# old_contorol_board.net
KiCad netlist of a schematic drawn in EAGLE
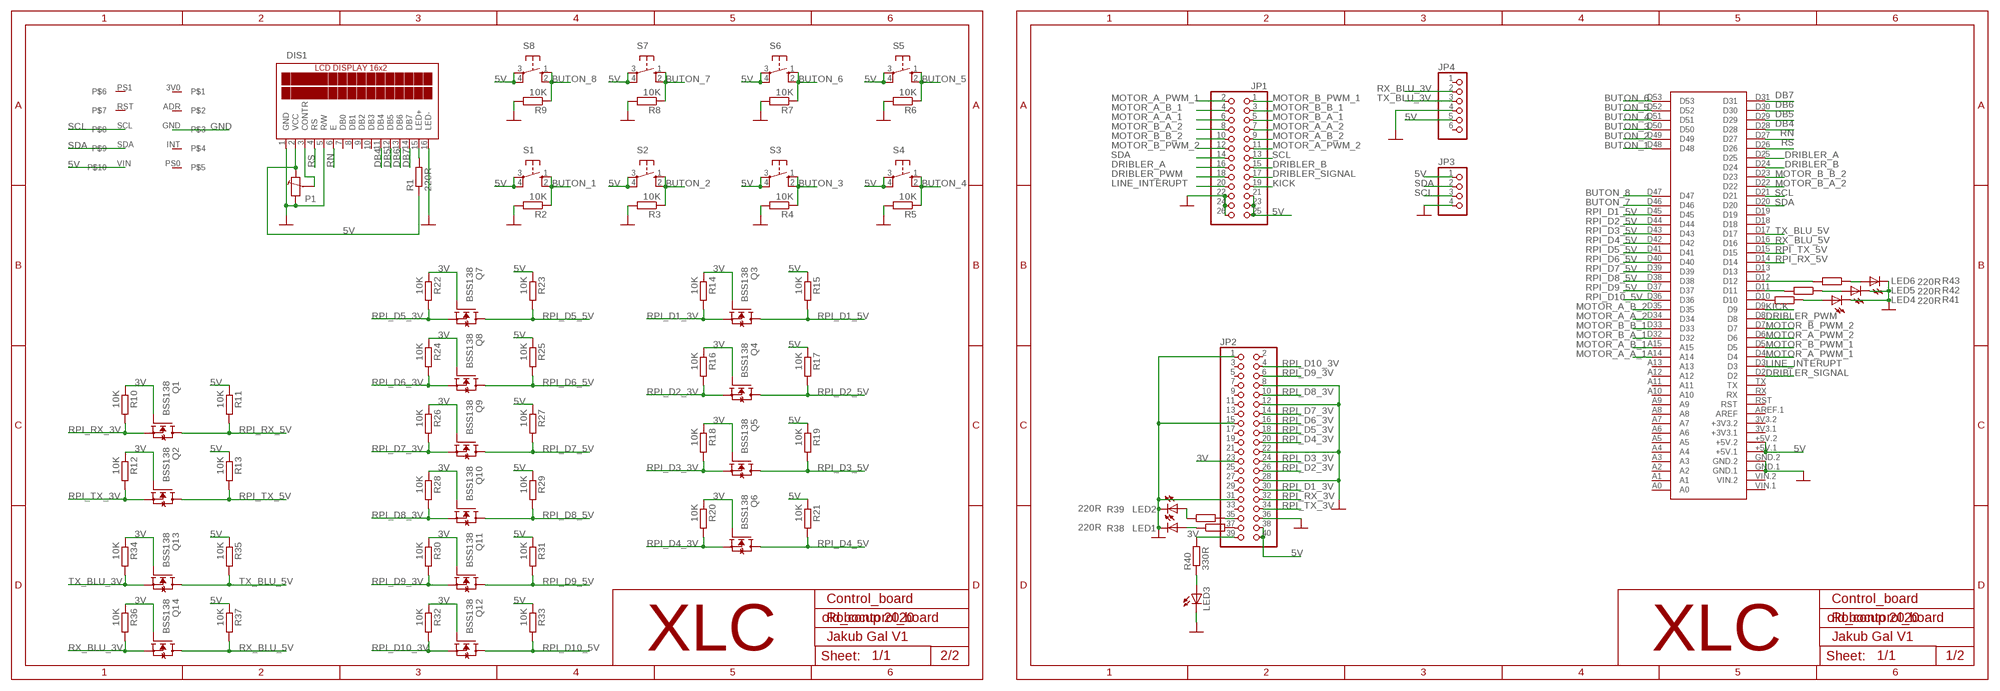
[diagram p0: schematic, sheet 1]

(export (version "E")
  (design (tool "Eeschema 10.0.6"))
  (components
    (comp (ref "DIS1")
      (value "LCD_DISPLEJ_16X2Z")
      (footprint "eagle-import:LCD_DISPLEJ_16X2")
      (libsource (lib "eagle-import") (part "LCD_DISPLEJ_16X2Z"))
    )
    (comp (ref "JP1")
      (value "PINHD-2X13_2.54")
      (footprint "eagle-import:2X13")
      (libsource (lib "eagle-import") (part "PINHD-2X13_2.54"))
    )
    (comp (ref "JP2")
      (value "PINHD-2X20_2.54")
      (footprint "eagle-import:2X20")
      (libsource (lib "eagle-import") (part "PINHD-2X20_2.54"))
    )
    (comp (ref "JP3")
      (value "PINHD-1X4_2.54")
      (footprint "eagle-import:1X04")
      (libsource (lib "eagle-import") (part "PINHD-1X4_2.54"))
    )
    (comp (ref "JP4")
      (value "PINHD-1X6_2.54")
      (footprint "eagle-import:1X06")
      (libsource (lib "eagle-import") (part "PINHD-1X6_2.54"))
    )
    (comp (ref "LED1")
      (value "LEDCHIPLED_0603")
      (footprint "eagle-import:CHIPLED_0603")
      (libsource (lib "eagle-import") (part "LEDCHIPLED_0603"))
    )
    (comp (ref "LED2")
      (value "LEDCHIPLED_0603")
      (footprint "eagle-import:CHIPLED_0603")
      (libsource (lib "eagle-import") (part "LEDCHIPLED_0603"))
    )
    (comp (ref "LED3")
      (value "LEDCHIPLED_0603")
      (footprint "eagle-import:CHIPLED_0603")
      (libsource (lib "eagle-import") (part "LEDCHIPLED_0603"))
    )
    (comp (ref "LED4")
      (value "LEDCHIPLED_0603")
      (footprint "eagle-import:CHIPLED_0603")
      (libsource (lib "eagle-import") (part "LEDCHIPLED_0603"))
    )
    (comp (ref "LED5")
      (value "LEDCHIPLED_0603")
      (footprint "eagle-import:CHIPLED_0603")
      (libsource (lib "eagle-import") (part "LEDCHIPLED_0603"))
    )
    (comp (ref "LED6")
      (value "LEDCHIPLED_0603")
      (footprint "eagle-import:CHIPLED_0603")
      (libsource (lib "eagle-import") (part "LEDCHIPLED_0603"))
    )
    (comp (ref "P1")
      (value "TRIMER-CA6V")
      (footprint "eagle-import:TP-CA6V")
      (libsource (lib "eagle-import") (part "TRIMER-CA6V"))
    )
    (comp (ref "Q1")
      (value "BSS138")
      (footprint "eagle-import:SOT23")
      (fields (field (name "MF") "Fairchild"))
      (libsource (lib "eagle-import") (part "BSS138"))
    )
    (comp (ref "Q2")
      (value "BSS138")
      (footprint "eagle-import:SOT23")
      (fields (field (name "MF") "Fairchild"))
      (libsource (lib "eagle-import") (part "BSS138"))
    )
    (comp (ref "Q3")
      (value "BSS138")
      (footprint "eagle-import:SOT23")
      (fields (field (name "MF") "Fairchild"))
      (libsource (lib "eagle-import") (part "BSS138"))
    )
    (comp (ref "Q4")
      (value "BSS138")
      (footprint "eagle-import:SOT23")
      (fields (field (name "MF") "Fairchild"))
      (libsource (lib "eagle-import") (part "BSS138"))
    )
    (comp (ref "Q5")
      (value "BSS138")
      (footprint "eagle-import:SOT23")
      (fields (field (name "MF") "Fairchild"))
      (libsource (lib "eagle-import") (part "BSS138"))
    )
    (comp (ref "Q6")
      (value "BSS138")
      (footprint "eagle-import:SOT23")
      (fields (field (name "MF") "Fairchild"))
      (libsource (lib "eagle-import") (part "BSS138"))
    )
    (comp (ref "Q7")
      (value "BSS138")
      (footprint "eagle-import:SOT23")
      (fields (field (name "MF") "Fairchild"))
      (libsource (lib "eagle-import") (part "BSS138"))
    )
    (comp (ref "Q8")
      (value "BSS138")
      (footprint "eagle-import:SOT23")
      (fields (field (name "MF") "Fairchild"))
      (libsource (lib "eagle-import") (part "BSS138"))
    )
    (comp (ref "Q9")
      (value "BSS138")
      (footprint "eagle-import:SOT23")
      (fields (field (name "MF") "Fairchild"))
      (libsource (lib "eagle-import") (part "BSS138"))
    )
    (comp (ref "Q10")
      (value "BSS138")
      (footprint "eagle-import:SOT23")
      (fields (field (name "MF") "Fairchild"))
      (libsource (lib "eagle-import") (part "BSS138"))
    )
    (comp (ref "Q11")
      (value "BSS138")
      (footprint "eagle-import:SOT23")
      (fields (field (name "MF") "Fairchild"))
      (libsource (lib "eagle-import") (part "BSS138"))
    )
    (comp (ref "Q12")
      (value "BSS138")
      (footprint "eagle-import:SOT23")
      (fields (field (name "MF") "Fairchild"))
      (libsource (lib "eagle-import") (part "BSS138"))
    )
    (comp (ref "Q13")
      (value "BSS138")
      (footprint "eagle-import:SOT23")
      (fields (field (name "MF") "Fairchild"))
      (libsource (lib "eagle-import") (part "BSS138"))
    )
    (comp (ref "Q14")
      (value "BSS138")
      (footprint "eagle-import:SOT23")
      (fields (field (name "MF") "Fairchild"))
      (libsource (lib "eagle-import") (part "BSS138"))
    )
    (comp (ref "R1")
      (value "220R")
      (footprint "eagle-import:R0603")
      (libsource (lib "eagle-import") (part "R-EU_R0603"))
    )
    (comp (ref "R2")
      (value "10K")
      (footprint "eagle-import:R0603")
      (libsource (lib "eagle-import") (part "R-EU_R0603"))
    )
    (comp (ref "R3")
      (value "10K")
      (footprint "eagle-import:R0603")
      (libsource (lib "eagle-import") (part "R-EU_R0603"))
    )
    (comp (ref "R4")
      (value "10K")
      (footprint "eagle-import:R0603")
      (libsource (lib "eagle-import") (part "R-EU_R0603"))
    )
    (comp (ref "R5")
      (value "10K")
      (footprint "eagle-import:R0603")
      (libsource (lib "eagle-import") (part "R-EU_R0603"))
    )
    (comp (ref "R6")
      (value "10K")
      (footprint "eagle-import:R0603")
      (libsource (lib "eagle-import") (part "R-EU_R0603"))
    )
    (comp (ref "R7")
      (value "10K")
      (footprint "eagle-import:R0603")
      (libsource (lib "eagle-import") (part "R-EU_R0603"))
    )
    (comp (ref "R8")
      (value "10K")
      (footprint "eagle-import:R0603")
      (libsource (lib "eagle-import") (part "R-EU_R0603"))
    )
    (comp (ref "R9")
      (value "10K")
      (footprint "eagle-import:R0603")
      (libsource (lib "eagle-import") (part "R-EU_R0603"))
    )
    (comp (ref "R10")
      (value "10K")
      (footprint "eagle-import:R0603")
      (libsource (lib "eagle-import") (part "R-EU_R0603"))
    )
    (comp (ref "R11")
      (value "10K")
      (footprint "eagle-import:R0603")
      (libsource (lib "eagle-import") (part "R-EU_R0603"))
    )
    (comp (ref "R12")
      (value "10K")
      (footprint "eagle-import:R0603")
      (libsource (lib "eagle-import") (part "R-EU_R0603"))
    )
    (comp (ref "R13")
      (value "10K")
      (footprint "eagle-import:R0603")
      (libsource (lib "eagle-import") (part "R-EU_R0603"))
    )
    (comp (ref "R14")
      (value "10K")
      (footprint "eagle-import:R0603")
      (libsource (lib "eagle-import") (part "R-EU_R0603"))
    )
    (comp (ref "R15")
      (value "10K")
      (footprint "eagle-import:R0603")
      (libsource (lib "eagle-import") (part "R-EU_R0603"))
    )
    (comp (ref "R16")
      (value "10K")
      (footprint "eagle-import:R0603")
      (libsource (lib "eagle-import") (part "R-EU_R0603"))
    )
    (comp (ref "R17")
      (value "10K")
      (footprint "eagle-import:R0603")
      (libsource (lib "eagle-import") (part "R-EU_R0603"))
    )
    (comp (ref "R18")
      (value "10K")
      (footprint "eagle-import:R0603")
      (libsource (lib "eagle-import") (part "R-EU_R0603"))
    )
    (comp (ref "R19")
      (value "10K")
      (footprint "eagle-import:R0603")
      (libsource (lib "eagle-import") (part "R-EU_R0603"))
    )
    (comp (ref "R20")
      (value "10K")
      (footprint "eagle-import:R0603")
      (libsource (lib "eagle-import") (part "R-EU_R0603"))
    )
    (comp (ref "R21")
      (value "10K")
      (footprint "eagle-import:R0603")
      (libsource (lib "eagle-import") (part "R-EU_R0603"))
    )
    (comp (ref "R22")
      (value "10K")
      (footprint "eagle-import:R0603")
      (libsource (lib "eagle-import") (part "R-EU_R0603"))
    )
    (comp (ref "R23")
      (value "10K")
      (footprint "eagle-import:R0603")
      (libsource (lib "eagle-import") (part "R-EU_R0603"))
    )
    (comp (ref "R24")
      (value "10K")
      (footprint "eagle-import:R0603")
      (libsource (lib "eagle-import") (part "R-EU_R0603"))
    )
    (comp (ref "R25")
      (value "10K")
      (footprint "eagle-import:R0603")
      (libsource (lib "eagle-import") (part "R-EU_R0603"))
    )
    (comp (ref "R26")
      (value "10K")
      (footprint "eagle-import:R0603")
      (libsource (lib "eagle-import") (part "R-EU_R0603"))
    )
    (comp (ref "R27")
      (value "10K")
      (footprint "eagle-import:R0603")
      (libsource (lib "eagle-import") (part "R-EU_R0603"))
    )
    (comp (ref "R28")
      (value "10K")
      (footprint "eagle-import:R0603")
      (libsource (lib "eagle-import") (part "R-EU_R0603"))
    )
    (comp (ref "R29")
      (value "10K")
      (footprint "eagle-import:R0603")
      (libsource (lib "eagle-import") (part "R-EU_R0603"))
    )
    (comp (ref "R30")
      (value "10K")
      (footprint "eagle-import:R0603")
      (libsource (lib "eagle-import") (part "R-EU_R0603"))
    )
    (comp (ref "R31")
      (value "10K")
      (footprint "eagle-import:R0603")
      (libsource (lib "eagle-import") (part "R-EU_R0603"))
    )
    (comp (ref "R32")
      (value "10K")
      (footprint "eagle-import:R0603")
      (libsource (lib "eagle-import") (part "R-EU_R0603"))
    )
    (comp (ref "R33")
      (value "10K")
      (footprint "eagle-import:R0603")
      (libsource (lib "eagle-import") (part "R-EU_R0603"))
    )
    (comp (ref "R34")
      (value "10K")
      (footprint "eagle-import:R0603")
      (libsource (lib "eagle-import") (part "R-EU_R0603"))
    )
    (comp (ref "R35")
      (value "10K")
      (footprint "eagle-import:R0603")
      (libsource (lib "eagle-import") (part "R-EU_R0603"))
    )
    (comp (ref "R36")
      (value "10K")
      (footprint "eagle-import:R0603")
      (libsource (lib "eagle-import") (part "R-EU_R0603"))
    )
    (comp (ref "R37")
      (value "10K")
      (footprint "eagle-import:R0603")
      (libsource (lib "eagle-import") (part "R-EU_R0603"))
    )
    (comp (ref "R38")
      (value "220R")
      (footprint "eagle-import:R0603")
      (libsource (lib "eagle-import") (part "R-EU_R0603"))
    )
    (comp (ref "R39")
      (value "220R")
      (footprint "eagle-import:R0603")
      (libsource (lib "eagle-import") (part "R-EU_R0603"))
    )
    (comp (ref "R40")
      (value "330R")
      (footprint "eagle-import:R0603")
      (libsource (lib "eagle-import") (part "R-EU_R0603"))
    )
    (comp (ref "R41")
      (value "220R")
      (footprint "eagle-import:R0603")
      (libsource (lib "eagle-import") (part "R-EU_R0603"))
    )
    (comp (ref "R42")
      (value "220R")
      (footprint "eagle-import:R0603")
      (libsource (lib "eagle-import") (part "R-EU_R0603"))
    )
    (comp (ref "R43")
      (value "220R")
      (footprint "eagle-import:R0603")
      (libsource (lib "eagle-import") (part "R-EU_R0603"))
    )
    (comp (ref "S1")
      (value "10-XX")
      (footprint "eagle-import:B3F-10XX")
      (fields (field (name "MPN") "B3F-1000"))
      (libsource (lib "eagle-import") (part "10-XX"))
    )
    (comp (ref "S2")
      (value "10-XX")
      (footprint "eagle-import:B3F-10XX")
      (fields (field (name "MPN") "B3F-1000"))
      (libsource (lib "eagle-import") (part "10-XX"))
    )
    (comp (ref "S3")
      (value "10-XX")
      (footprint "eagle-import:B3F-10XX")
      (fields (field (name "MPN") "B3F-1000"))
      (libsource (lib "eagle-import") (part "10-XX"))
    )
    (comp (ref "S4")
      (value "10-XX")
      (footprint "eagle-import:B3F-10XX")
      (fields (field (name "MPN") "B3F-1000"))
      (libsource (lib "eagle-import") (part "10-XX"))
    )
    (comp (ref "S5")
      (value "10-XX")
      (footprint "eagle-import:B3F-10XX")
      (fields (field (name "MPN") "B3F-1000"))
      (libsource (lib "eagle-import") (part "10-XX"))
    )
    (comp (ref "S6")
      (value "10-XX")
      (footprint "eagle-import:B3F-10XX")
      (fields (field (name "MPN") "B3F-1000"))
      (libsource (lib "eagle-import") (part "10-XX"))
    )
    (comp (ref "S7")
      (value "10-XX")
      (footprint "eagle-import:B3F-10XX")
      (fields (field (name "MPN") "B3F-1000"))
      (libsource (lib "eagle-import") (part "10-XX"))
    )
    (comp (ref "S8")
      (value "10-XX")
      (footprint "eagle-import:B3F-10XX")
      (fields (field (name "MPN") "B3F-1000"))
      (libsource (lib "eagle-import") (part "10-XX"))
    )
    (comp (ref "U$1")
      (value "MEGA2560_MIKRO")
      (footprint "eagle-import:MEGA2560_MIKRO")
      (libsource (lib "eagle-import") (part "MEGA2560_MIKRO"))
    )
    (comp (ref "U$2")
      (value "BNO055")
      (footprint "eagle-import:BNO005")
      (libsource (lib "eagle-import") (part "BNO055"))
    )
  )
  (nets
    (net (code "1") (name "/3V") (class "Default")
      (node (ref "JP2") (pin "23") (pinfunction "23_23") (pintype "passive"))
      (node (ref "JP2") (pin "39") (pinfunction "39_39") (pintype "passive"))
      (node (ref "Q1") (pin "1") (pinfunction "G_1") (pintype "passive"))
      (node (ref "Q10") (pin "1") (pinfunction "G_1") (pintype "passive"))
      (node (ref "Q11") (pin "1") (pinfunction "G_1") (pintype "passive"))
      (node (ref "Q12") (pin "1") (pinfunction "G_1") (pintype "passive"))
      (node (ref "Q13") (pin "1") (pinfunction "G_1") (pintype "passive"))
      (node (ref "Q14") (pin "1") (pinfunction "G_1") (pintype "passive"))
      (node (ref "Q2") (pin "1") (pinfunction "G_1") (pintype "passive"))
      (node (ref "Q3") (pin "1") (pinfunction "G_1") (pintype "passive"))
      (node (ref "Q4") (pin "1") (pinfunction "G_1") (pintype "passive"))
      (node (ref "Q5") (pin "1") (pinfunction "G_1") (pintype "passive"))
      (node (ref "Q6") (pin "1") (pinfunction "G_1") (pintype "passive"))
      (node (ref "Q7") (pin "1") (pinfunction "G_1") (pintype "passive"))
      (node (ref "Q8") (pin "1") (pinfunction "G_1") (pintype "passive"))
      (node (ref "Q9") (pin "1") (pinfunction "G_1") (pintype "passive"))
      (node (ref "R10") (pin "1") (pinfunction "1_1") (pintype "passive"))
      (node (ref "R12") (pin "1") (pinfunction "1_1") (pintype "passive"))
      (node (ref "R14") (pin "1") (pinfunction "1_1") (pintype "passive"))
      (node (ref "R16") (pin "1") (pinfunction "1_1") (pintype "passive"))
      (node (ref "R18") (pin "1") (pinfunction "1_1") (pintype "passive"))
      (node (ref "R20") (pin "1") (pinfunction "1_1") (pintype "passive"))
      (node (ref "R22") (pin "1") (pinfunction "1_1") (pintype "passive"))
      (node (ref "R24") (pin "1") (pinfunction "1_1") (pintype "passive"))
      (node (ref "R26") (pin "1") (pinfunction "1_1") (pintype "passive"))
      (node (ref "R28") (pin "1") (pinfunction "1_1") (pintype "passive"))
      (node (ref "R30") (pin "1") (pinfunction "1_1") (pintype "passive"))
      (node (ref "R32") (pin "1") (pinfunction "1_1") (pintype "passive"))
      (node (ref "R34") (pin "1") (pinfunction "1_1") (pintype "passive"))
      (node (ref "R36") (pin "1") (pinfunction "1_1") (pintype "passive"))
      (node (ref "R40") (pin "2") (pinfunction "2_2") (pintype "passive"))
    )
    (net (code "2") (name "/5V") (class "Default")
      (node (ref "DIS1") (pin "2") (pinfunction "VCC_2") (pintype "power_in"))
      (node (ref "JP1") (pin "21") (pinfunction "21_21") (pintype "passive"))
      (node (ref "JP1") (pin "23") (pinfunction "23_23") (pintype "passive"))
      (node (ref "JP1") (pin "25") (pinfunction "25_25") (pintype "passive"))
      (node (ref "JP2") (pin "38") (pinfunction "38_38") (pintype "passive"))
      (node (ref "JP2") (pin "40") (pinfunction "40_40") (pintype "passive"))
      (node (ref "JP3") (pin "1") (pinfunction "1_1") (pintype "passive"))
      (node (ref "JP4") (pin "5") (pinfunction "5_5") (pintype "passive"))
      (node (ref "P1") (pin "2") (pinfunction "2_2") (pintype "passive"))
      (node (ref "R1") (pin "1") (pinfunction "1_1") (pintype "passive"))
      (node (ref "R11") (pin "1") (pinfunction "1_1") (pintype "passive"))
      (node (ref "R13") (pin "1") (pinfunction "1_1") (pintype "passive"))
      (node (ref "R15") (pin "1") (pinfunction "1_1") (pintype "passive"))
      (node (ref "R17") (pin "1") (pinfunction "1_1") (pintype "passive"))
      (node (ref "R19") (pin "1") (pinfunction "1_1") (pintype "passive"))
      (node (ref "R21") (pin "1") (pinfunction "1_1") (pintype "passive"))
      (node (ref "R23") (pin "1") (pinfunction "1_1") (pintype "passive"))
      (node (ref "R25") (pin "1") (pinfunction "1_1") (pintype "passive"))
      (node (ref "R27") (pin "1") (pinfunction "1_1") (pintype "passive"))
      (node (ref "R29") (pin "1") (pinfunction "1_1") (pintype "passive"))
      (node (ref "R31") (pin "1") (pinfunction "1_1") (pintype "passive"))
      (node (ref "R33") (pin "1") (pinfunction "1_1") (pintype "passive"))
      (node (ref "R35") (pin "1") (pinfunction "1_1") (pintype "passive"))
      (node (ref "R37") (pin "1") (pinfunction "1_1") (pintype "passive"))
      (node (ref "S1") (pin "3") (pinfunction "P_3") (pintype "passive"))
      (node (ref "S1") (pin "4") (pinfunction "P1_4") (pintype "passive"))
      (node (ref "S2") (pin "3") (pinfunction "P_3") (pintype "passive"))
      (node (ref "S2") (pin "4") (pinfunction "P1_4") (pintype "passive"))
      (node (ref "S3") (pin "3") (pinfunction "P_3") (pintype "passive"))
      (node (ref "S3") (pin "4") (pinfunction "P1_4") (pintype "passive"))
      (node (ref "S4") (pin "3") (pinfunction "P_3") (pintype "passive"))
      (node (ref "S4") (pin "4") (pinfunction "P1_4") (pintype "passive"))
      (node (ref "S5") (pin "3") (pinfunction "P_3") (pintype "passive"))
      (node (ref "S5") (pin "4") (pinfunction "P1_4") (pintype "passive"))
      (node (ref "S6") (pin "3") (pinfunction "P_3") (pintype "passive"))
      (node (ref "S6") (pin "4") (pinfunction "P1_4") (pintype "passive"))
      (node (ref "S7") (pin "3") (pinfunction "P_3") (pintype "passive"))
      (node (ref "S7") (pin "4") (pinfunction "P1_4") (pintype "passive"))
      (node (ref "S8") (pin "3") (pinfunction "P_3") (pintype "passive"))
      (node (ref "S8") (pin "4") (pinfunction "P1_4") (pintype "passive"))
      (node (ref "U$1") (pin "+5V.1") (pinfunction "+5V.1_+5V.1") (pintype "bidirectional"))
      (node (ref "U$1") (pin "+5V.2") (pinfunction "+5V.2_+5V.2") (pintype "bidirectional"))
      (node (ref "U$2") (pin "VIN") (pinfunction "P$10_VIN") (pintype "bidirectional"))
    )
    (net (code "3") (name "/BUTON_1") (class "Default")
      (node (ref "R2") (pin "1") (pinfunction "1_1") (pintype "passive"))
      (node (ref "S1") (pin "1") (pinfunction "S_1") (pintype "passive"))
      (node (ref "S1") (pin "2") (pinfunction "S1_2") (pintype "passive"))
      (node (ref "U$1") (pin "D48") (pinfunction "D48_D48") (pintype "bidirectional"))
    )
    (net (code "4") (name "/BUTON_2") (class "Default")
      (node (ref "R3") (pin "1") (pinfunction "1_1") (pintype "passive"))
      (node (ref "S2") (pin "1") (pinfunction "S_1") (pintype "passive"))
      (node (ref "S2") (pin "2") (pinfunction "S1_2") (pintype "passive"))
      (node (ref "U$1") (pin "D49") (pinfunction "D49_D49") (pintype "bidirectional"))
    )
    (net (code "5") (name "/BUTON_3") (class "Default")
      (node (ref "R4") (pin "1") (pinfunction "1_1") (pintype "passive"))
      (node (ref "S3") (pin "1") (pinfunction "S_1") (pintype "passive"))
      (node (ref "S3") (pin "2") (pinfunction "S1_2") (pintype "passive"))
      (node (ref "U$1") (pin "D50") (pinfunction "D50_D50") (pintype "bidirectional"))
    )
    (net (code "6") (name "/BUTON_4") (class "Default")
      (node (ref "R5") (pin "1") (pinfunction "1_1") (pintype "passive"))
      (node (ref "S4") (pin "1") (pinfunction "S_1") (pintype "passive"))
      (node (ref "S4") (pin "2") (pinfunction "S1_2") (pintype "passive"))
      (node (ref "U$1") (pin "D51") (pinfunction "D51_D51") (pintype "bidirectional"))
    )
    (net (code "7") (name "/BUTON_5") (class "Default")
      (node (ref "R6") (pin "1") (pinfunction "1_1") (pintype "passive"))
      (node (ref "S5") (pin "1") (pinfunction "S_1") (pintype "passive"))
      (node (ref "S5") (pin "2") (pinfunction "S1_2") (pintype "passive"))
      (node (ref "U$1") (pin "D52") (pinfunction "D52_D52") (pintype "bidirectional"))
    )
    (net (code "8") (name "/BUTON_6") (class "Default")
      (node (ref "R7") (pin "1") (pinfunction "1_1") (pintype "passive"))
      (node (ref "S6") (pin "1") (pinfunction "S_1") (pintype "passive"))
      (node (ref "S6") (pin "2") (pinfunction "S1_2") (pintype "passive"))
      (node (ref "U$1") (pin "D53") (pinfunction "D53_D53") (pintype "bidirectional"))
    )
    (net (code "9") (name "/BUTON_7") (class "Default")
      (node (ref "R8") (pin "1") (pinfunction "1_1") (pintype "passive"))
      (node (ref "S7") (pin "1") (pinfunction "S_1") (pintype "passive"))
      (node (ref "S7") (pin "2") (pinfunction "S1_2") (pintype "passive"))
      (node (ref "U$1") (pin "D46") (pinfunction "D46_D46") (pintype "bidirectional"))
    )
    (net (code "10") (name "/BUTON_8") (class "Default")
      (node (ref "R9") (pin "1") (pinfunction "1_1") (pintype "passive"))
      (node (ref "S8") (pin "1") (pinfunction "S_1") (pintype "passive"))
      (node (ref "S8") (pin "2") (pinfunction "S1_2") (pintype "passive"))
      (node (ref "U$1") (pin "D47") (pinfunction "D47_D47") (pintype "bidirectional"))
    )
    (net (code "11") (name "/DB4") (class "Default")
      (node (ref "DIS1") (pin "11") (pinfunction "DB4_11") (pintype "bidirectional"))
      (node (ref "U$1") (pin "D28") (pinfunction "D28_D28") (pintype "bidirectional"))
    )
    (net (code "12") (name "/DB5") (class "Default")
      (node (ref "DIS1") (pin "12") (pinfunction "DB5_12") (pintype "bidirectional"))
      (node (ref "U$1") (pin "D29") (pinfunction "D29_D29") (pintype "bidirectional"))
    )
    (net (code "13") (name "/DB6") (class "Default")
      (node (ref "DIS1") (pin "13") (pinfunction "DB6_13") (pintype "bidirectional"))
      (node (ref "U$1") (pin "D30") (pinfunction "D30_D30") (pintype "bidirectional"))
    )
    (net (code "14") (name "/DB7") (class "Default")
      (node (ref "DIS1") (pin "14") (pinfunction "DB7_14") (pintype "bidirectional"))
      (node (ref "U$1") (pin "D31") (pinfunction "D31_D31") (pintype "bidirectional"))
    )
    (net (code "15") (name "/DRIBLER_A") (class "Default")
      (node (ref "JP1") (pin "16") (pinfunction "16_16") (pintype "passive"))
      (node (ref "U$1") (pin "D25") (pinfunction "D25_D25") (pintype "bidirectional"))
    )
    (net (code "16") (name "/DRIBLER_B") (class "Default")
      (node (ref "JP1") (pin "15") (pinfunction "15_15") (pintype "passive"))
      (node (ref "U$1") (pin "D24") (pinfunction "D24_D24") (pintype "bidirectional"))
    )
    (net (code "17") (name "/DRIBLER_PWM") (class "Default")
      (node (ref "JP1") (pin "18") (pinfunction "18_18") (pintype "passive"))
      (node (ref "U$1") (pin "D8") (pinfunction "D8_D8") (pintype "bidirectional"))
    )
    (net (code "18") (name "/DRIBLER_SIGNAL") (class "Default")
      (node (ref "JP1") (pin "17") (pinfunction "17_17") (pintype "passive"))
      (node (ref "U$1") (pin "D2") (pinfunction "D2_D2") (pintype "bidirectional"))
    )
    (net (code "19") (name "/KICK") (class "Default")
      (node (ref "JP1") (pin "19") (pinfunction "19_19") (pintype "passive"))
      (node (ref "U$1") (pin "D9") (pinfunction "D9_D9") (pintype "bidirectional"))
    )
    (net (code "20") (name "/LINE_INTERUPT") (class "Default")
      (node (ref "JP1") (pin "20") (pinfunction "20_20") (pintype "passive"))
      (node (ref "U$1") (pin "D3") (pinfunction "D3_D3") (pintype "bidirectional"))
    )
    (net (code "21") (name "/MOTOR_A_A_1") (class "Default")
      (node (ref "JP1") (pin "6") (pinfunction "6_6") (pintype "passive"))
      (node (ref "U$1") (pin "A14") (pinfunction "A14_A14") (pintype "bidirectional"))
    )
    (net (code "22") (name "/MOTOR_A_A_2") (class "Default")
      (node (ref "JP1") (pin "7") (pinfunction "7_7") (pintype "passive"))
      (node (ref "U$1") (pin "D34") (pinfunction "D34_D34") (pintype "bidirectional"))
    )
    (net (code "23") (name "/MOTOR_A_B_1") (class "Default")
      (node (ref "JP1") (pin "4") (pinfunction "4_4") (pintype "passive"))
      (node (ref "U$1") (pin "A15") (pinfunction "A15_A15") (pintype "bidirectional"))
    )
    (net (code "24") (name "/MOTOR_A_B_2") (class "Default")
      (node (ref "JP1") (pin "9") (pinfunction "9_9") (pintype "passive"))
      (node (ref "U$1") (pin "D35") (pinfunction "D35_D35") (pintype "bidirectional"))
    )
    (net (code "25") (name "/MOTOR_A_PWM_1") (class "Default")
      (node (ref "JP1") (pin "2") (pinfunction "2_2") (pintype "passive"))
      (node (ref "U$1") (pin "D4") (pinfunction "D4_D4") (pintype "bidirectional"))
    )
    (net (code "26") (name "/MOTOR_A_PWM_2") (class "Default")
      (node (ref "JP1") (pin "11") (pinfunction "11_11") (pintype "passive"))
      (node (ref "U$1") (pin "D6") (pinfunction "D6_D6") (pintype "bidirectional"))
    )
    (net (code "27") (name "/MOTOR_B_A_1") (class "Default")
      (node (ref "JP1") (pin "5") (pinfunction "5_5") (pintype "passive"))
      (node (ref "U$1") (pin "D32") (pinfunction "D32_D32") (pintype "bidirectional"))
    )
    (net (code "28") (name "/MOTOR_B_A_2") (class "Default")
      (node (ref "JP1") (pin "8") (pinfunction "8_8") (pintype "passive"))
      (node (ref "U$1") (pin "D22") (pinfunction "D22_D22") (pintype "bidirectional"))
    )
    (net (code "29") (name "/MOTOR_B_B_1") (class "Default")
      (node (ref "JP1") (pin "3") (pinfunction "3_3") (pintype "passive"))
      (node (ref "U$1") (pin "D33") (pinfunction "D33_D33") (pintype "bidirectional"))
    )
    (net (code "30") (name "/MOTOR_B_B_2") (class "Default")
      (node (ref "JP1") (pin "10") (pinfunction "10_10") (pintype "passive"))
      (node (ref "U$1") (pin "D23") (pinfunction "D23_D23") (pintype "bidirectional"))
    )
    (net (code "31") (name "/MOTOR_B_PWM_1") (class "Default")
      (node (ref "JP1") (pin "1") (pinfunction "1_1") (pintype "passive"))
      (node (ref "U$1") (pin "D5") (pinfunction "D5_D5") (pintype "bidirectional"))
    )
    (net (code "32") (name "/MOTOR_B_PWM_2") (class "Default")
      (node (ref "JP1") (pin "12") (pinfunction "12_12") (pintype "passive"))
      (node (ref "U$1") (pin "D7") (pinfunction "D7_D7") (pintype "bidirectional"))
    )
    (net (code "33") (name "/RN") (class "Default")
      (node (ref "DIS1") (pin "6") (pinfunction "E_6") (pintype "input"))
      (node (ref "U$1") (pin "D27") (pinfunction "D27_D27") (pintype "bidirectional"))
    )
    (net (code "34") (name "/RPI_D1_3V") (class "Default")
      (node (ref "JP2") (pin "30") (pinfunction "30_30") (pintype "passive"))
      (node (ref "Q3") (pin "2") (pinfunction "S_2") (pintype "passive"))
      (node (ref "R14") (pin "2") (pinfunction "2_2") (pintype "passive"))
    )
    (net (code "35") (name "/RPI_D1_5V") (class "Default")
      (node (ref "Q3") (pin "3") (pinfunction "D_3") (pintype "passive"))
      (node (ref "R15") (pin "2") (pinfunction "2_2") (pintype "passive"))
      (node (ref "U$1") (pin "D45") (pinfunction "D45_D45") (pintype "bidirectional"))
    )
    (net (code "36") (name "/RPI_D2_3V") (class "Default")
      (node (ref "JP2") (pin "26") (pinfunction "26_26") (pintype "passive"))
      (node (ref "Q4") (pin "2") (pinfunction "S_2") (pintype "passive"))
      (node (ref "R16") (pin "2") (pinfunction "2_2") (pintype "passive"))
    )
    (net (code "37") (name "/RPI_D2_5V") (class "Default")
      (node (ref "Q4") (pin "3") (pinfunction "D_3") (pintype "passive"))
      (node (ref "R17") (pin "2") (pinfunction "2_2") (pintype "passive"))
      (node (ref "U$1") (pin "D44") (pinfunction "D44_D44") (pintype "bidirectional"))
    )
    (net (code "38") (name "/RPI_D3_3V") (class "Default")
      (node (ref "JP2") (pin "24") (pinfunction "24_24") (pintype "passive"))
      (node (ref "Q5") (pin "2") (pinfunction "S_2") (pintype "passive"))
      (node (ref "R18") (pin "2") (pinfunction "2_2") (pintype "passive"))
    )
    (net (code "39") (name "/RPI_D3_5V") (class "Default")
      (node (ref "Q5") (pin "3") (pinfunction "D_3") (pintype "passive"))
      (node (ref "R19") (pin "2") (pinfunction "2_2") (pintype "passive"))
      (node (ref "U$1") (pin "D43") (pinfunction "D43_D43") (pintype "bidirectional"))
    )
    (net (code "40") (name "/RPI_D4_3V") (class "Default")
      (node (ref "JP2") (pin "20") (pinfunction "20_20") (pintype "passive"))
      (node (ref "Q6") (pin "2") (pinfunction "S_2") (pintype "passive"))
      (node (ref "R20") (pin "2") (pinfunction "2_2") (pintype "passive"))
    )
    (net (code "41") (name "/RPI_D4_5V") (class "Default")
      (node (ref "Q6") (pin "3") (pinfunction "D_3") (pintype "passive"))
      (node (ref "R21") (pin "2") (pinfunction "2_2") (pintype "passive"))
      (node (ref "U$1") (pin "D42") (pinfunction "D42_D42") (pintype "bidirectional"))
    )
    (net (code "42") (name "/RPI_D5_3V") (class "Default")
      (node (ref "JP2") (pin "18") (pinfunction "18_18") (pintype "passive"))
      (node (ref "Q7") (pin "2") (pinfunction "S_2") (pintype "passive"))
      (node (ref "R22") (pin "2") (pinfunction "2_2") (pintype "passive"))
    )
    (net (code "43") (name "/RPI_D5_5V") (class "Default")
      (node (ref "Q7") (pin "3") (pinfunction "D_3") (pintype "passive"))
      (node (ref "R23") (pin "2") (pinfunction "2_2") (pintype "passive"))
      (node (ref "U$1") (pin "D41") (pinfunction "D41_D41") (pintype "bidirectional"))
    )
    (net (code "44") (name "/RPI_D6_3V") (class "Default")
      (node (ref "JP2") (pin "16") (pinfunction "16_16") (pintype "passive"))
      (node (ref "Q8") (pin "2") (pinfunction "S_2") (pintype "passive"))
      (node (ref "R24") (pin "2") (pinfunction "2_2") (pintype "passive"))
    )
    (net (code "45") (name "/RPI_D6_5V") (class "Default")
      (node (ref "Q8") (pin "3") (pinfunction "D_3") (pintype "passive"))
      (node (ref "R25") (pin "2") (pinfunction "2_2") (pintype "passive"))
      (node (ref "U$1") (pin "D40") (pinfunction "D40_D40") (pintype "bidirectional"))
    )
    (net (code "46") (name "/RPI_D7_3V") (class "Default")
      (node (ref "JP2") (pin "14") (pinfunction "14_14") (pintype "passive"))
      (node (ref "Q9") (pin "2") (pinfunction "S_2") (pintype "passive"))
      (node (ref "R26") (pin "2") (pinfunction "2_2") (pintype "passive"))
    )
    (net (code "47") (name "/RPI_D7_5V") (class "Default")
      (node (ref "Q9") (pin "3") (pinfunction "D_3") (pintype "passive"))
      (node (ref "R27") (pin "2") (pinfunction "2_2") (pintype "passive"))
      (node (ref "U$1") (pin "D39") (pinfunction "D39_D39") (pintype "bidirectional"))
    )
    (net (code "48") (name "/RPI_D8_3V") (class "Default")
      (node (ref "JP2") (pin "10") (pinfunction "10_10") (pintype "passive"))
      (node (ref "Q10") (pin "2") (pinfunction "S_2") (pintype "passive"))
      (node (ref "R28") (pin "2") (pinfunction "2_2") (pintype "passive"))
    )
    (net (code "49") (name "/RPI_D8_5V") (class "Default")
      (node (ref "Q10") (pin "3") (pinfunction "D_3") (pintype "passive"))
      (node (ref "R29") (pin "2") (pinfunction "2_2") (pintype "passive"))
      (node (ref "U$1") (pin "D38") (pinfunction "D38_D38") (pintype "bidirectional"))
    )
    (net (code "50") (name "/RPI_D9_3V") (class "Default")
      (node (ref "JP2") (pin "6") (pinfunction "6_6") (pintype "passive"))
      (node (ref "Q11") (pin "2") (pinfunction "S_2") (pintype "passive"))
      (node (ref "R30") (pin "2") (pinfunction "2_2") (pintype "passive"))
    )
    (net (code "51") (name "/RPI_D9_5V") (class "Default")
      (node (ref "Q11") (pin "3") (pinfunction "D_3") (pintype "passive"))
      (node (ref "R31") (pin "2") (pinfunction "2_2") (pintype "passive"))
      (node (ref "U$1") (pin "D37") (pinfunction "D37_D37") (pintype "bidirectional"))
    )
    (net (code "52") (name "/RPI_D10_3V") (class "Default")
      (node (ref "JP2") (pin "4") (pinfunction "4_4") (pintype "passive"))
      (node (ref "Q12") (pin "2") (pinfunction "S_2") (pintype "passive"))
      (node (ref "R32") (pin "2") (pinfunction "2_2") (pintype "passive"))
    )
    (net (code "53") (name "/RPI_D10_5V") (class "Default")
      (node (ref "Q12") (pin "3") (pinfunction "D_3") (pintype "passive"))
      (node (ref "R33") (pin "2") (pinfunction "2_2") (pintype "passive"))
      (node (ref "U$1") (pin "D36") (pinfunction "D36_D36") (pintype "bidirectional"))
    )
    (net (code "54") (name "/RPI_RX_3V") (class "Default")
      (node (ref "JP2") (pin "32") (pinfunction "32_32") (pintype "passive"))
      (node (ref "Q1") (pin "2") (pinfunction "S_2") (pintype "passive"))
      (node (ref "R10") (pin "2") (pinfunction "2_2") (pintype "passive"))
    )
    (net (code "55") (name "/RPI_RX_5V") (class "Default")
      (node (ref "Q1") (pin "3") (pinfunction "D_3") (pintype "passive"))
      (node (ref "R11") (pin "2") (pinfunction "2_2") (pintype "passive"))
      (node (ref "U$1") (pin "D14") (pinfunction "D14_D14") (pintype "bidirectional"))
    )
    (net (code "56") (name "/RPI_TX_3V") (class "Default")
      (node (ref "JP2") (pin "34") (pinfunction "34_34") (pintype "passive"))
      (node (ref "Q2") (pin "2") (pinfunction "S_2") (pintype "passive"))
      (node (ref "R12") (pin "2") (pinfunction "2_2") (pintype "passive"))
    )
    (net (code "57") (name "/RPI_TX_5V") (class "Default")
      (node (ref "Q2") (pin "3") (pinfunction "D_3") (pintype "passive"))
      (node (ref "R13") (pin "2") (pinfunction "2_2") (pintype "passive"))
      (node (ref "U$1") (pin "D15") (pinfunction "D15_D15") (pintype "bidirectional"))
    )
    (net (code "58") (name "/RS") (class "Default")
      (node (ref "DIS1") (pin "4") (pinfunction "RS_4") (pintype "input"))
      (node (ref "U$1") (pin "D26") (pinfunction "D26_D26") (pintype "bidirectional"))
    )
    (net (code "59") (name "/RX_BLU_3V") (class "Default")
      (node (ref "JP4") (pin "2") (pinfunction "2_2") (pintype "passive"))
      (node (ref "Q14") (pin "2") (pinfunction "S_2") (pintype "passive"))
      (node (ref "R36") (pin "2") (pinfunction "2_2") (pintype "passive"))
    )
    (net (code "60") (name "/RX_BLU_5V") (class "Default")
      (node (ref "Q14") (pin "3") (pinfunction "D_3") (pintype "passive"))
      (node (ref "R37") (pin "2") (pinfunction "2_2") (pintype "passive"))
      (node (ref "U$1") (pin "D16") (pinfunction "D16_D16") (pintype "bidirectional"))
    )
    (net (code "61") (name "/SCL") (class "Default")
      (node (ref "JP1") (pin "13") (pinfunction "13_13") (pintype "passive"))
      (node (ref "JP3") (pin "3") (pinfunction "3_3") (pintype "passive"))
      (node (ref "U$1") (pin "D21") (pinfunction "D21_D21") (pintype "bidirectional"))
      (node (ref "U$2") (pin "SCL") (pinfunction "P$8_SCL") (pintype "bidirectional"))
    )
    (net (code "62") (name "/SDA") (class "Default")
      (node (ref "JP1") (pin "14") (pinfunction "14_14") (pintype "passive"))
      (node (ref "JP3") (pin "2") (pinfunction "2_2") (pintype "passive"))
      (node (ref "U$1") (pin "D20") (pinfunction "D20_D20") (pintype "bidirectional"))
      (node (ref "U$2") (pin "SDA") (pinfunction "P$9_SDA") (pintype "bidirectional"))
    )
    (net (code "63") (name "/TX_BLU_3V") (class "Default")
      (node (ref "JP4") (pin "3") (pinfunction "3_3") (pintype "passive"))
      (node (ref "Q13") (pin "2") (pinfunction "S_2") (pintype "passive"))
      (node (ref "R34") (pin "2") (pinfunction "2_2") (pintype "passive"))
    )
    (net (code "64") (name "/TX_BLU_5V") (class "Default")
      (node (ref "Q13") (pin "3") (pinfunction "D_3") (pintype "passive"))
      (node (ref "R35") (pin "2") (pinfunction "2_2") (pintype "passive"))
      (node (ref "U$1") (pin "D17") (pinfunction "D17_D17") (pintype "bidirectional"))
    )
    (net (code "65") (name "GND") (class "Default")
      (node (ref "DIS1") (pin "1") (pinfunction "GND_1") (pintype "power_in"))
      (node (ref "DIS1") (pin "16") (pinfunction "LED-_16") (pintype "passive"))
      (node (ref "DIS1") (pin "5") (pinfunction "R/W_5") (pintype "input"))
      (node (ref "JP1") (pin "22") (pinfunction "22_22") (pintype "passive"))
      (node (ref "JP1") (pin "24") (pinfunction "24_24") (pintype "passive"))
      (node (ref "JP1") (pin "26") (pinfunction "26_26") (pintype "passive"))
      (node (ref "JP2") (pin "1") (pinfunction "1_1") (pintype "passive"))
      (node (ref "JP2") (pin "12") (pinfunction "12_12") (pintype "passive"))
      (node (ref "JP2") (pin "15") (pinfunction "15_15") (pintype "passive"))
      (node (ref "JP2") (pin "22") (pinfunction "22_22") (pintype "passive"))
      (node (ref "JP2") (pin "28") (pinfunction "28_28") (pintype "passive"))
      (node (ref "JP2") (pin "31") (pinfunction "31_31") (pintype "passive"))
      (node (ref "JP2") (pin "36") (pinfunction "36_36") (pintype "passive"))
      (node (ref "JP2") (pin "8") (pinfunction "8_8") (pintype "passive"))
      (node (ref "JP3") (pin "4") (pinfunction "4_4") (pintype "passive"))
      (node (ref "JP4") (pin "4") (pinfunction "4_4") (pintype "passive"))
      (node (ref "LED1") (pin "C") (pinfunction "C_C") (pintype "passive"))
      (node (ref "LED2") (pin "C") (pinfunction "C_C") (pintype "passive"))
      (node (ref "LED3") (pin "C") (pinfunction "C_C") (pintype "passive"))
      (node (ref "LED4") (pin "C") (pinfunction "C_C") (pintype "passive"))
      (node (ref "LED5") (pin "C") (pinfunction "C_C") (pintype "passive"))
      (node (ref "LED6") (pin "C") (pinfunction "C_C") (pintype "passive"))
      (node (ref "P1") (pin "1") (pinfunction "1_1") (pintype "passive"))
      (node (ref "R2") (pin "2") (pinfunction "2_2") (pintype "passive"))
      (node (ref "R3") (pin "2") (pinfunction "2_2") (pintype "passive"))
      (node (ref "R4") (pin "2") (pinfunction "2_2") (pintype "passive"))
      (node (ref "R5") (pin "2") (pinfunction "2_2") (pintype "passive"))
      (node (ref "R6") (pin "2") (pinfunction "2_2") (pintype "passive"))
      (node (ref "R7") (pin "2") (pinfunction "2_2") (pintype "passive"))
      (node (ref "R8") (pin "2") (pinfunction "2_2") (pintype "passive"))
      (node (ref "R9") (pin "2") (pinfunction "2_2") (pintype "passive"))
      (node (ref "U$1") (pin "GND.1") (pinfunction "GND.1_GND.1") (pintype "bidirectional"))
      (node (ref "U$1") (pin "GND.2") (pinfunction "GND.2_GND.2") (pintype "bidirectional"))
      (node (ref "U$2") (pin "GND") (pinfunction "P$3_GND") (pintype "bidirectional"))
    )
    (net (code "66") (name "Net-(DIS1-CONTR)") (class "Default")
      (node (ref "DIS1") (pin "3") (pinfunction "CONTR_3") (pintype "input"))
      (node (ref "P1") (pin "BEZ") (pinfunction "BEZ_BEZ") (pintype "passive"))
    )
    (net (code "67") (name "Net-(DIS1-LED+)") (class "Default")
      (node (ref "DIS1") (pin "15") (pinfunction "LED+_15") (pintype "passive"))
      (node (ref "R1") (pin "2") (pinfunction "2_2") (pintype "passive"))
    )
    (net (code "68") (name "Net-(JP2-Pad35)") (class "Default")
      (node (ref "JP2") (pin "35") (pinfunction "35_35") (pintype "passive"))
      (node (ref "R39") (pin "2") (pinfunction "2_2") (pintype "passive"))
    )
    (net (code "69") (name "Net-(JP2-Pad37)") (class "Default")
      (node (ref "JP2") (pin "37") (pinfunction "37_37") (pintype "passive"))
      (node (ref "R38") (pin "2") (pinfunction "2_2") (pintype "passive"))
    )
    (net (code "70") (name "Net-(LED1-PadA)") (class "Default")
      (node (ref "LED1") (pin "A") (pinfunction "A_A") (pintype "passive"))
      (node (ref "R38") (pin "1") (pinfunction "1_1") (pintype "passive"))
    )
    (net (code "71") (name "Net-(LED2-PadA)") (class "Default")
      (node (ref "LED2") (pin "A") (pinfunction "A_A") (pintype "passive"))
      (node (ref "R39") (pin "1") (pinfunction "1_1") (pintype "passive"))
    )
    (net (code "72") (name "Net-(LED3-PadA)") (class "Default")
      (node (ref "LED3") (pin "A") (pinfunction "A_A") (pintype "passive"))
      (node (ref "R40") (pin "1") (pinfunction "1_1") (pintype "passive"))
    )
    (net (code "73") (name "Net-(LED4-PadA)") (class "Default")
      (node (ref "LED4") (pin "A") (pinfunction "A_A") (pintype "passive"))
      (node (ref "R41") (pin "1") (pinfunction "1_1") (pintype "passive"))
    )
    (net (code "74") (name "Net-(LED5-PadA)") (class "Default")
      (node (ref "LED5") (pin "A") (pinfunction "A_A") (pintype "passive"))
      (node (ref "R42") (pin "1") (pinfunction "1_1") (pintype "passive"))
    )
    (net (code "75") (name "Net-(LED6-PadA)") (class "Default")
      (node (ref "LED6") (pin "A") (pinfunction "A_A") (pintype "passive"))
      (node (ref "R43") (pin "1") (pinfunction "1_1") (pintype "passive"))
    )
    (net (code "76") (name "Net-(R41-Pad2)") (class "Default")
      (node (ref "R41") (pin "2") (pinfunction "2_2") (pintype "passive"))
      (node (ref "U$1") (pin "D10") (pinfunction "D10_D10") (pintype "bidirectional"))
    )
    (net (code "77") (name "Net-(R42-Pad2)") (class "Default")
      (node (ref "R42") (pin "2") (pinfunction "2_2") (pintype "passive"))
      (node (ref "U$1") (pin "D11") (pinfunction "D11_D11") (pintype "bidirectional"))
    )
    (net (code "78") (name "Net-(R43-Pad2)") (class "Default")
      (node (ref "R43") (pin "2") (pinfunction "2_2") (pintype "passive"))
      (node (ref "U$1") (pin "D12") (pinfunction "D12_D12") (pintype "bidirectional"))
    )
    (net (code "79") (name "unconnected-(DIS1-DB0-Pad7)") (class "Default")
      (node (ref "DIS1") (pin "7") (pinfunction "DB0_7") (pintype "bidirectional"))
    )
    (net (code "80") (name "unconnected-(DIS1-DB1-Pad8)") (class "Default")
      (node (ref "DIS1") (pin "8") (pinfunction "DB1_8") (pintype "bidirectional"))
    )
    (net (code "81") (name "unconnected-(DIS1-DB2-Pad9)") (class "Default")
      (node (ref "DIS1") (pin "9") (pinfunction "DB2_9") (pintype "bidirectional"))
    )
    (net (code "82") (name "unconnected-(DIS1-DB3-Pad10)") (class "Default")
      (node (ref "DIS1") (pin "10") (pinfunction "DB3_10") (pintype "bidirectional"))
    )
    (net (code "83") (name "unconnected-(JP2-Pad2)") (class "Default")
      (node (ref "JP2") (pin "2") (pinfunction "2_2") (pintype "passive"))
    )
    (net (code "84") (name "unconnected-(JP2-Pad3)") (class "Default")
      (node (ref "JP2") (pin "3") (pinfunction "3_3") (pintype "passive"))
    )
    (net (code "85") (name "unconnected-(JP2-Pad5)") (class "Default")
      (node (ref "JP2") (pin "5") (pinfunction "5_5") (pintype "passive"))
    )
    (net (code "86") (name "unconnected-(JP2-Pad7)") (class "Default")
      (node (ref "JP2") (pin "7") (pinfunction "7_7") (pintype "passive"))
    )
    (net (code "87") (name "unconnected-(JP2-Pad9)") (class "Default")
      (node (ref "JP2") (pin "9") (pinfunction "9_9") (pintype "passive"))
    )
    (net (code "88") (name "unconnected-(JP2-Pad11)") (class "Default")
      (node (ref "JP2") (pin "11") (pinfunction "11_11") (pintype "passive"))
    )
    (net (code "89") (name "unconnected-(JP2-Pad13)") (class "Default")
      (node (ref "JP2") (pin "13") (pinfunction "13_13") (pintype "passive"))
    )
    (net (code "90") (name "unconnected-(JP2-Pad17)") (class "Default")
      (node (ref "JP2") (pin "17") (pinfunction "17_17") (pintype "passive"))
    )
    (net (code "91") (name "unconnected-(JP2-Pad19)") (class "Default")
      (node (ref "JP2") (pin "19") (pinfunction "19_19") (pintype "passive"))
    )
    (net (code "92") (name "unconnected-(JP2-Pad21)") (class "Default")
      (node (ref "JP2") (pin "21") (pinfunction "21_21") (pintype "passive"))
    )
    (net (code "93") (name "unconnected-(JP2-Pad25)") (class "Default")
      (node (ref "JP2") (pin "25") (pinfunction "25_25") (pintype "passive"))
    )
    (net (code "94") (name "unconnected-(JP2-Pad27)") (class "Default")
      (node (ref "JP2") (pin "27") (pinfunction "27_27") (pintype "passive"))
    )
    (net (code "95") (name "unconnected-(JP2-Pad29)") (class "Default")
      (node (ref "JP2") (pin "29") (pinfunction "29_29") (pintype "passive"))
    )
    (net (code "96") (name "unconnected-(JP2-Pad33)") (class "Default")
      (node (ref "JP2") (pin "33") (pinfunction "33_33") (pintype "passive"))
    )
    (net (code "97") (name "unconnected-(JP4-Pad1)") (class "Default")
      (node (ref "JP4") (pin "1") (pinfunction "1_1") (pintype "passive"))
    )
    (net (code "98") (name "unconnected-(JP4-Pad6)") (class "Default")
      (node (ref "JP4") (pin "6") (pinfunction "6_6") (pintype "passive"))
    )
    (net (code "99") (name "unconnected-(U$1-+3V3.1-Pad3V3.1)") (class "Default")
      (node (ref "U$1") (pin "3V3.1") (pinfunction "+3V3.1_3V3.1") (pintype "bidirectional"))
    )
    (net (code "100") (name "unconnected-(U$1-+3V3.2-Pad3V3.2)") (class "Default")
      (node (ref "U$1") (pin "3V3.2") (pinfunction "+3V3.2_3V3.2") (pintype "bidirectional"))
    )
    (net (code "101") (name "unconnected-(U$1-AREF-PadAREF.1)") (class "Default")
      (node (ref "U$1") (pin "AREF.1") (pinfunction "AREF_AREF.1") (pintype "bidirectional"))
    )
    (net (code "102") (name "unconnected-(U$1-PadA0)") (class "Default")
      (node (ref "U$1") (pin "A0") (pinfunction "A0_A0") (pintype "bidirectional"))
    )
    (net (code "103") (name "unconnected-(U$1-PadA1)") (class "Default")
      (node (ref "U$1") (pin "A1") (pinfunction "A1_A1") (pintype "bidirectional"))
    )
    (net (code "104") (name "unconnected-(U$1-PadA2)") (class "Default")
      (node (ref "U$1") (pin "A2") (pinfunction "A2_A2") (pintype "bidirectional"))
    )
    (net (code "105") (name "unconnected-(U$1-PadA3)") (class "Default")
      (node (ref "U$1") (pin "A3") (pinfunction "A3_A3") (pintype "bidirectional"))
    )
    (net (code "106") (name "unconnected-(U$1-PadA4)") (class "Default")
      (node (ref "U$1") (pin "A4") (pinfunction "A4_A4") (pintype "bidirectional"))
    )
    (net (code "107") (name "unconnected-(U$1-PadA5)") (class "Default")
      (node (ref "U$1") (pin "A5") (pinfunction "A5_A5") (pintype "bidirectional"))
    )
    (net (code "108") (name "unconnected-(U$1-PadA6)") (class "Default")
      (node (ref "U$1") (pin "A6") (pinfunction "A6_A6") (pintype "bidirectional"))
    )
    (net (code "109") (name "unconnected-(U$1-PadA7)") (class "Default")
      (node (ref "U$1") (pin "A7") (pinfunction "A7_A7") (pintype "bidirectional"))
    )
    (net (code "110") (name "unconnected-(U$1-PadA8)") (class "Default")
      (node (ref "U$1") (pin "A8") (pinfunction "A8_A8") (pintype "bidirectional"))
    )
    (net (code "111") (name "unconnected-(U$1-PadA9)") (class "Default")
      (node (ref "U$1") (pin "A9") (pinfunction "A9_A9") (pintype "bidirectional"))
    )
    (net (code "112") (name "unconnected-(U$1-PadA10)") (class "Default")
      (node (ref "U$1") (pin "A10") (pinfunction "A10_A10") (pintype "bidirectional"))
    )
    (net (code "113") (name "unconnected-(U$1-PadA11)") (class "Default")
      (node (ref "U$1") (pin "A11") (pinfunction "A11_A11") (pintype "bidirectional"))
    )
    (net (code "114") (name "unconnected-(U$1-PadA12)") (class "Default")
      (node (ref "U$1") (pin "A12") (pinfunction "A12_A12") (pintype "bidirectional"))
    )
    (net (code "115") (name "unconnected-(U$1-PadA13)") (class "Default")
      (node (ref "U$1") (pin "A13") (pinfunction "A13_A13") (pintype "bidirectional"))
    )
    (net (code "116") (name "unconnected-(U$1-PadD13)") (class "Default")
      (node (ref "U$1") (pin "D13") (pinfunction "D13_D13") (pintype "bidirectional"))
    )
    (net (code "117") (name "unconnected-(U$1-PadD18)") (class "Default")
      (node (ref "U$1") (pin "D18") (pinfunction "D18_D18") (pintype "bidirectional"))
    )
    (net (code "118") (name "unconnected-(U$1-PadD19)") (class "Default")
      (node (ref "U$1") (pin "D19") (pinfunction "D19_D19") (pintype "bidirectional"))
    )
    (net (code "119") (name "unconnected-(U$1-PadRST)") (class "Default")
      (node (ref "U$1") (pin "RST") (pinfunction "RST_RST") (pintype "bidirectional"))
    )
    (net (code "120") (name "unconnected-(U$1-PadRX)") (class "Default")
      (node (ref "U$1") (pin "RX") (pinfunction "RX_RX") (pintype "bidirectional"))
    )
    (net (code "121") (name "unconnected-(U$1-PadTX)") (class "Default")
      (node (ref "U$1") (pin "TX") (pinfunction "TX_TX") (pintype "bidirectional"))
    )
    (net (code "122") (name "unconnected-(U$1-PadVIN.1)") (class "Default")
      (node (ref "U$1") (pin "VIN.1") (pinfunction "VIN.1_VIN.1") (pintype "bidirectional"))
    )
    (net (code "123") (name "unconnected-(U$1-PadVIN.2)") (class "Default")
      (node (ref "U$1") (pin "VIN.2") (pinfunction "VIN.2_VIN.2") (pintype "bidirectional"))
    )
    (net (code "124") (name "unconnected-(U$2-P$1-Pad3V0)") (class "Default")
      (node (ref "U$2") (pin "3V0") (pinfunction "P$1_3V0") (pintype "bidirectional"))
    )
    (net (code "125") (name "unconnected-(U$2-P$2-PadADR)") (class "Default")
      (node (ref "U$2") (pin "ADR") (pinfunction "P$2_ADR") (pintype "bidirectional"))
    )
    (net (code "126") (name "unconnected-(U$2-P$4-PadINT)") (class "Default")
      (node (ref "U$2") (pin "INT") (pinfunction "P$4_INT") (pintype "bidirectional"))
    )
    (net (code "127") (name "unconnected-(U$2-P$5-PadPS0)") (class "Default")
      (node (ref "U$2") (pin "PS0") (pinfunction "P$5_PS0") (pintype "bidirectional"))
    )
    (net (code "128") (name "unconnected-(U$2-P$6-PadPS1)") (class "Default")
      (node (ref "U$2") (pin "PS1") (pinfunction "P$6_PS1") (pintype "bidirectional"))
    )
    (net (code "129") (name "unconnected-(U$2-P$7-PadRST)") (class "Default")
      (node (ref "U$2") (pin "RST") (pinfunction "P$7_RST") (pintype "bidirectional"))
    )
  )
)
